# W021X.net
KiCad netlist of a schematic drawn in EAGLE
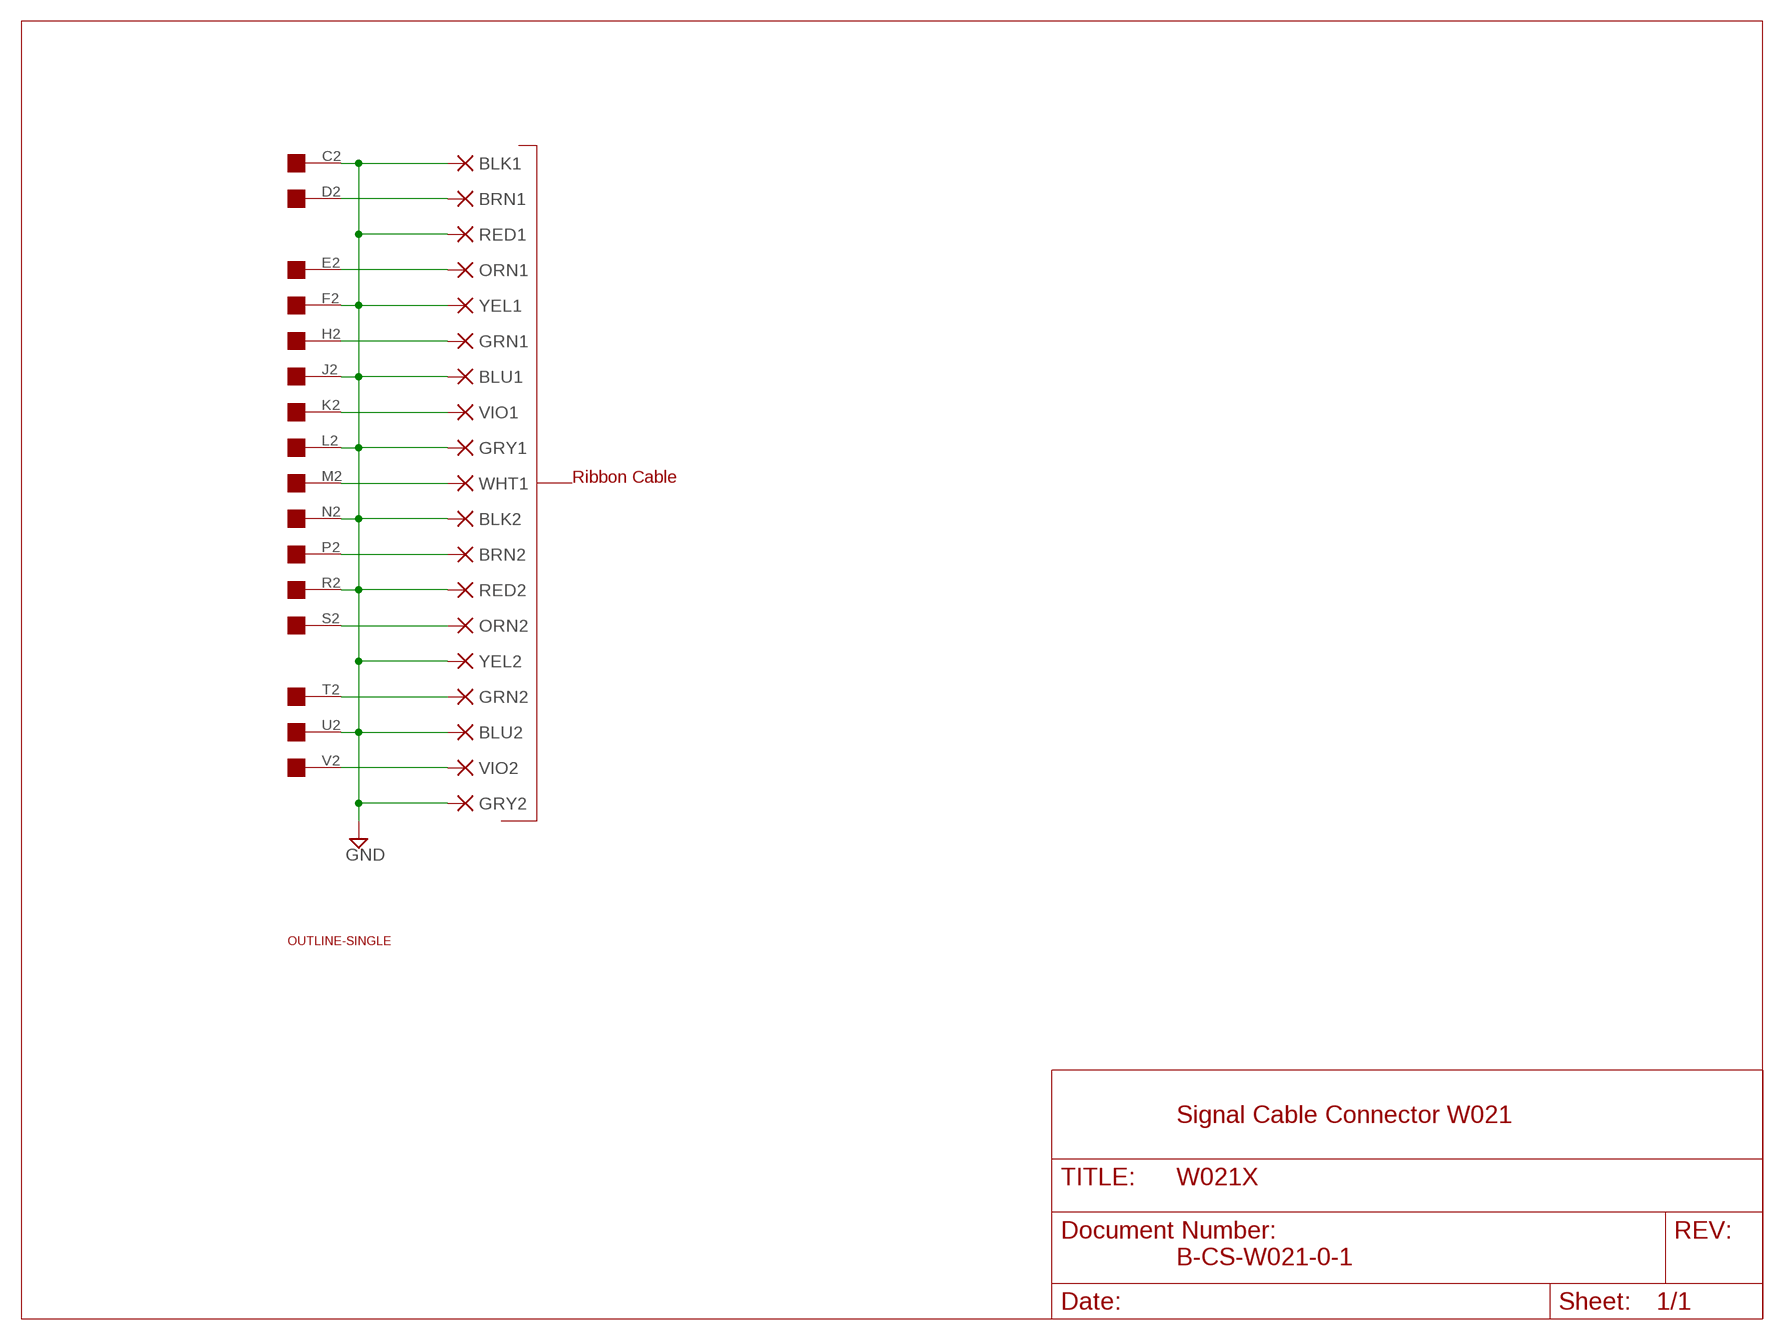
[diagram p0: schematic, sheet 1]

(export (version "E")
  (design (tool "Eeschema 10.0.6"))
  (components
    (comp (ref "BLK1")
      (value "PAD-0465")
      (footprint "eagle-import:0465")
      (libsource (lib "eagle-import") (part "PAD-0465"))
    )
    (comp (ref "BLK2")
      (value "PAD-0465")
      (footprint "eagle-import:0465")
      (libsource (lib "eagle-import") (part "PAD-0465"))
    )
    (comp (ref "BLU1")
      (value "PAD-0465")
      (footprint "eagle-import:0465")
      (libsource (lib "eagle-import") (part "PAD-0465"))
    )
    (comp (ref "BLU2")
      (value "PAD-0465")
      (footprint "eagle-import:0465")
      (libsource (lib "eagle-import") (part "PAD-0465"))
    )
    (comp (ref "BRN1")
      (value "PAD-0465")
      (footprint "eagle-import:0465")
      (libsource (lib "eagle-import") (part "PAD-0465"))
    )
    (comp (ref "BRN2")
      (value "PAD-0465")
      (footprint "eagle-import:0465")
      (libsource (lib "eagle-import") (part "PAD-0465"))
    )
    (comp (ref "GRN1")
      (value "PAD-0465")
      (footprint "eagle-import:0465")
      (libsource (lib "eagle-import") (part "PAD-0465"))
    )
    (comp (ref "GRN2")
      (value "PAD-0465")
      (footprint "eagle-import:0465")
      (libsource (lib "eagle-import") (part "PAD-0465"))
    )
    (comp (ref "GRY1")
      (value "PAD-0465")
      (footprint "eagle-import:0465")
      (libsource (lib "eagle-import") (part "PAD-0465"))
    )
    (comp (ref "GRY2")
      (value "PAD-0465")
      (footprint "eagle-import:0465")
      (libsource (lib "eagle-import") (part "PAD-0465"))
    )
    (comp (ref "ORN1")
      (value "PAD-0465")
      (footprint "eagle-import:0465")
      (libsource (lib "eagle-import") (part "PAD-0465"))
    )
    (comp (ref "ORN2")
      (value "PAD-0465")
      (footprint "eagle-import:0465")
      (libsource (lib "eagle-import") (part "PAD-0465"))
    )
    (comp (ref "RED1")
      (value "PAD-0465")
      (footprint "eagle-import:0465")
      (libsource (lib "eagle-import") (part "PAD-0465"))
    )
    (comp (ref "RED2")
      (value "PAD-0465")
      (footprint "eagle-import:0465")
      (libsource (lib "eagle-import") (part "PAD-0465"))
    )
    (comp (ref "U$1")
      (value "OUTLINE-SINGLE")
      (footprint "eagle-import:SINGLE")
      (libsource (lib "eagle-import") (part "OUTLINE-SINGLE"))
    )
    (comp (ref "U$2")
      (value "EDGE-1")
      (footprint "eagle-import:EDGE-CON1")
      (libsource (lib "eagle-import") (part "EDGE-1"))
    )
    (comp (ref "VIO1")
      (value "PAD-0465")
      (footprint "eagle-import:0465")
      (libsource (lib "eagle-import") (part "PAD-0465"))
    )
    (comp (ref "VIO2")
      (value "PAD-0465")
      (footprint "eagle-import:0465")
      (libsource (lib "eagle-import") (part "PAD-0465"))
    )
    (comp (ref "WHT1")
      (value "PAD-0465")
      (footprint "eagle-import:0465")
      (libsource (lib "eagle-import") (part "PAD-0465"))
    )
    (comp (ref "YEL1")
      (value "PAD-0465")
      (footprint "eagle-import:0465")
      (libsource (lib "eagle-import") (part "PAD-0465"))
    )
    (comp (ref "YEL2")
      (value "PAD-0465")
      (footprint "eagle-import:0465")
      (libsource (lib "eagle-import") (part "PAD-0465"))
    )
  )
  (nets
    (net (code "1") (name "GND") (class "Default")
      (node (ref "BLK1") (pin "P$1") (pinfunction "P_P$1") (pintype "passive"))
      (node (ref "BLK2") (pin "P$1") (pinfunction "P_P$1") (pintype "passive"))
      (node (ref "BLU1") (pin "P$1") (pinfunction "P_P$1") (pintype "passive"))
      (node (ref "BLU2") (pin "P$1") (pinfunction "P_P$1") (pintype "passive"))
      (node (ref "GRY1") (pin "P$1") (pinfunction "P_P$1") (pintype "passive"))
      (node (ref "GRY2") (pin "P$1") (pinfunction "P_P$1") (pintype "passive"))
      (node (ref "RED1") (pin "P$1") (pinfunction "P_P$1") (pintype "passive"))
      (node (ref "RED2") (pin "P$1") (pinfunction "P_P$1") (pintype "passive"))
      (node (ref "U$2") (pin "C2") (pinfunction "1_C2") (pintype "bidirectional"))
      (node (ref "U$2") (pin "F2") (pinfunction "1_F2") (pintype "bidirectional"))
      (node (ref "U$2") (pin "J2") (pinfunction "1_J2") (pintype "bidirectional"))
      (node (ref "U$2") (pin "L2") (pinfunction "1_L2") (pintype "bidirectional"))
      (node (ref "U$2") (pin "N2") (pinfunction "1_N2") (pintype "bidirectional"))
      (node (ref "U$2") (pin "R2") (pinfunction "1_R2") (pintype "bidirectional"))
      (node (ref "U$2") (pin "U2") (pinfunction "1_U2") (pintype "bidirectional"))
      (node (ref "YEL1") (pin "P$1") (pinfunction "P_P$1") (pintype "passive"))
      (node (ref "YEL2") (pin "P$1") (pinfunction "P_P$1") (pintype "passive"))
    )
    (net (code "2") (name "Net-(BRN1-P)") (class "Default")
      (node (ref "BRN1") (pin "P$1") (pinfunction "P_P$1") (pintype "passive"))
      (node (ref "U$2") (pin "D2") (pinfunction "1_D2") (pintype "bidirectional"))
    )
    (net (code "3") (name "Net-(BRN2-P)") (class "Default")
      (node (ref "BRN2") (pin "P$1") (pinfunction "P_P$1") (pintype "passive"))
      (node (ref "U$2") (pin "P2") (pinfunction "1_P2") (pintype "bidirectional"))
    )
    (net (code "4") (name "Net-(GRN1-P)") (class "Default")
      (node (ref "GRN1") (pin "P$1") (pinfunction "P_P$1") (pintype "passive"))
      (node (ref "U$2") (pin "H2") (pinfunction "1_H2") (pintype "bidirectional"))
    )
    (net (code "5") (name "Net-(GRN2-P)") (class "Default")
      (node (ref "GRN2") (pin "P$1") (pinfunction "P_P$1") (pintype "passive"))
      (node (ref "U$2") (pin "T2") (pinfunction "1_T2") (pintype "bidirectional"))
    )
    (net (code "6") (name "Net-(ORN1-P)") (class "Default")
      (node (ref "ORN1") (pin "P$1") (pinfunction "P_P$1") (pintype "passive"))
      (node (ref "U$2") (pin "E2") (pinfunction "1_E2") (pintype "bidirectional"))
    )
    (net (code "7") (name "Net-(ORN2-P)") (class "Default")
      (node (ref "ORN2") (pin "P$1") (pinfunction "P_P$1") (pintype "passive"))
      (node (ref "U$2") (pin "S2") (pinfunction "1_S2") (pintype "bidirectional"))
    )
    (net (code "8") (name "Net-(U$2I-1)") (class "Default")
      (node (ref "U$2") (pin "K2") (pinfunction "1_K2") (pintype "bidirectional"))
      (node (ref "VIO1") (pin "P$1") (pinfunction "P_P$1") (pintype "passive"))
    )
    (net (code "9") (name "Net-(U$2K-1)") (class "Default")
      (node (ref "U$2") (pin "M2") (pinfunction "1_M2") (pintype "bidirectional"))
      (node (ref "WHT1") (pin "P$1") (pinfunction "P_P$1") (pintype "passive"))
    )
    (net (code "10") (name "Net-(U$2R-1)") (class "Default")
      (node (ref "U$2") (pin "V2") (pinfunction "1_V2") (pintype "bidirectional"))
      (node (ref "VIO2") (pin "P$1") (pinfunction "P_P$1") (pintype "passive"))
    )
  )
)
